# Trig_to_Gate_Converter_main_V1.net
KiCad netlist of a schematic drawn in EAGLE
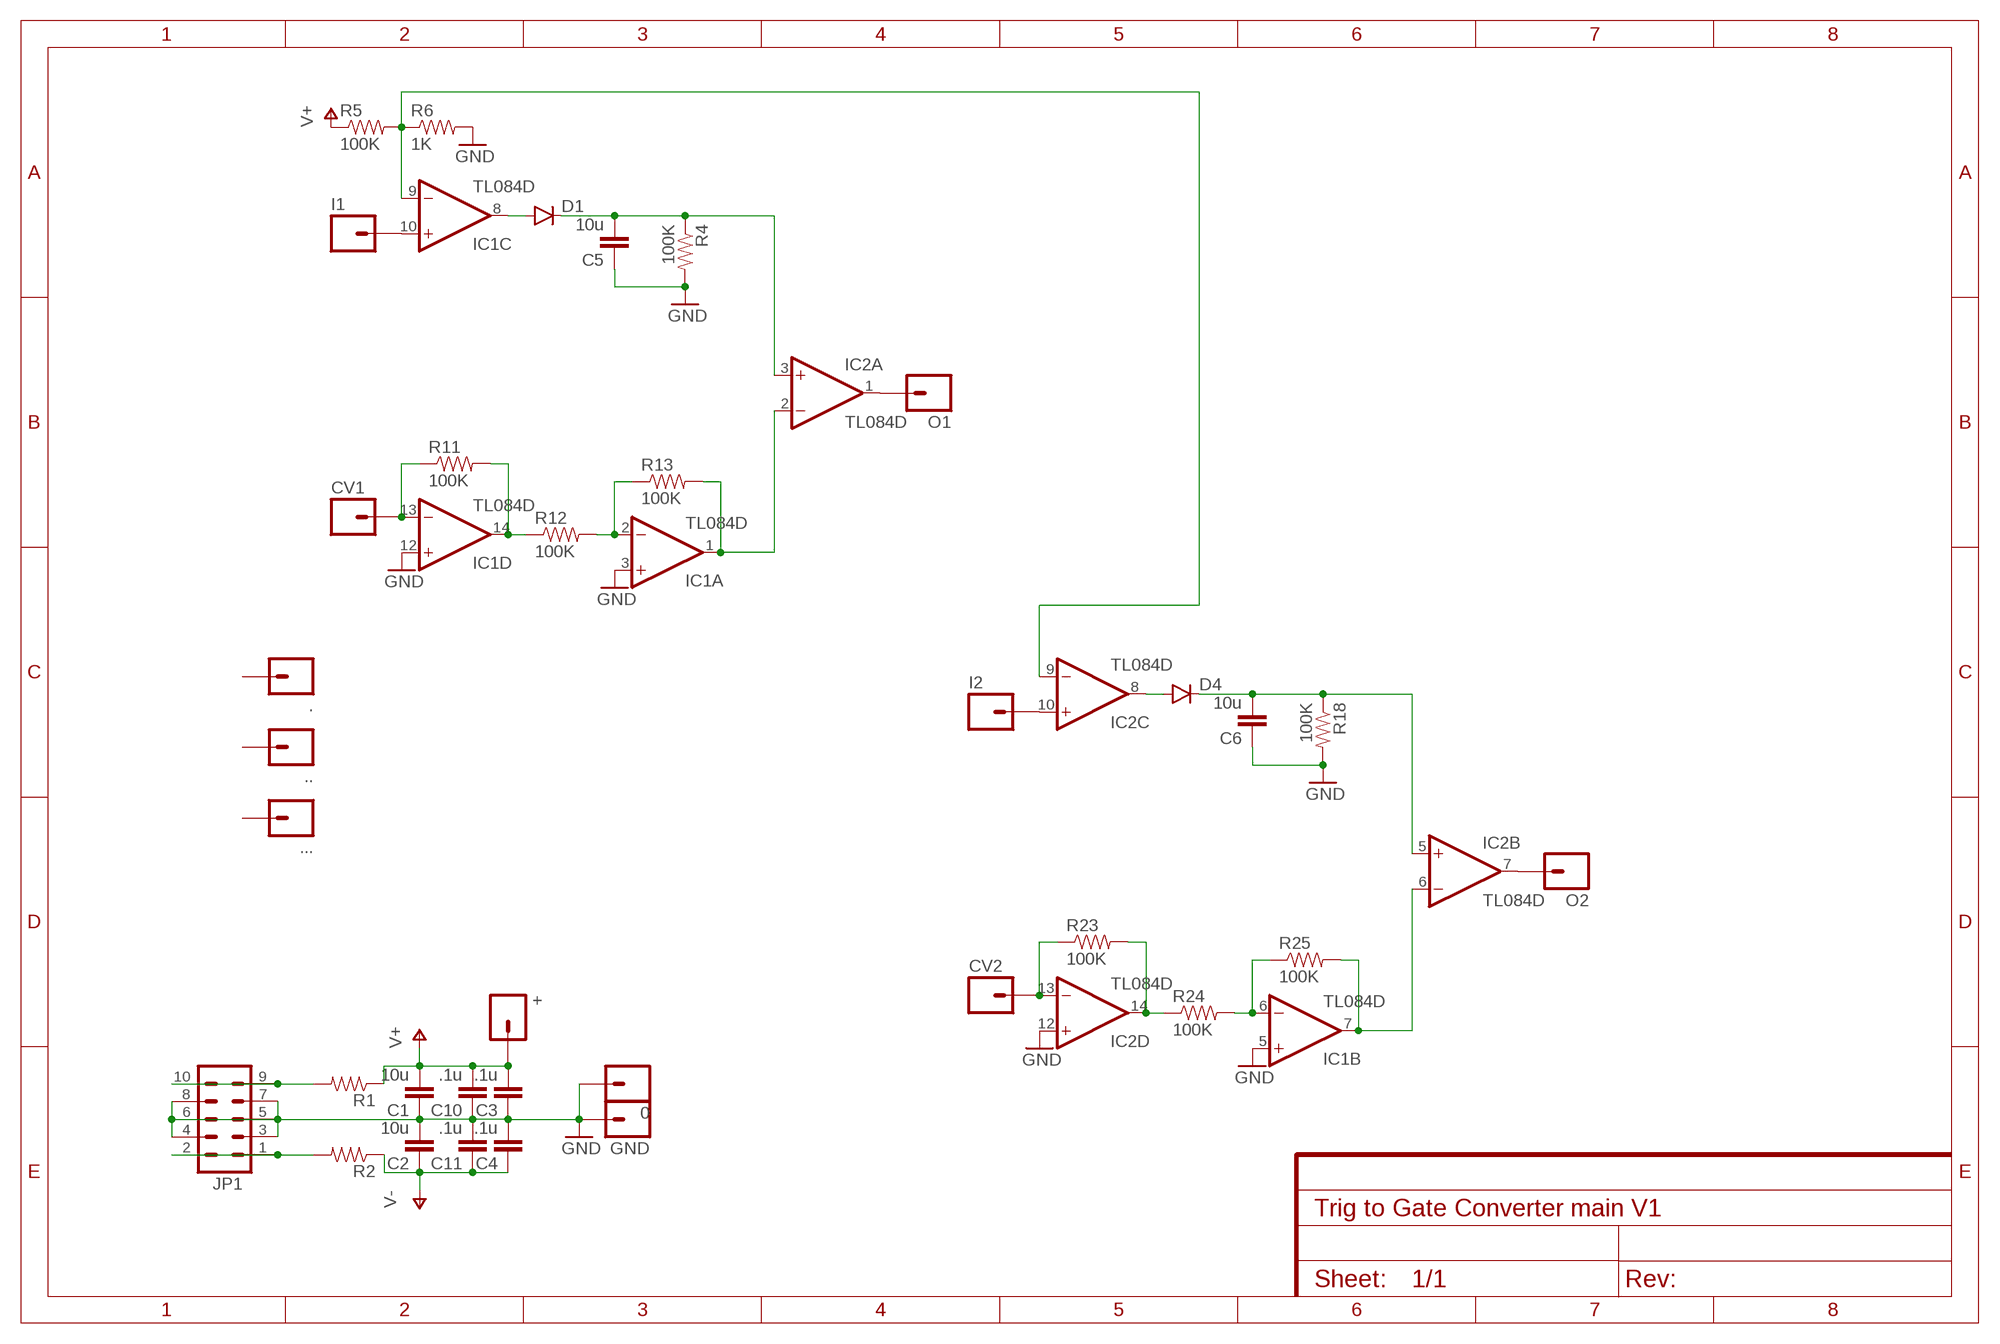
[diagram p0: schematic, sheet 1]

(export (version "E")
  (design (tool "Eeschema 10.0.6"))
  (components
    (comp (ref "+")
      (value "M01PTH")
      (footprint "eagle-import:1X01")
      (libsource (lib "eagle-import") (part "M01PTH"))
    )
    (comp (ref ".")
      (value "M01PTH")
      (footprint "eagle-import:1X01")
      (libsource (lib "eagle-import") (part "M01PTH"))
    )
    (comp (ref "..")
      (value "M01PTH")
      (footprint "eagle-import:1X01")
      (libsource (lib "eagle-import") (part "M01PTH"))
    )
    (comp (ref "...")
      (value "M01PTH")
      (footprint "eagle-import:1X01")
      (libsource (lib "eagle-import") (part "M01PTH"))
    )
    (comp (ref "0")
      (value "M01PTH")
      (footprint "eagle-import:1X01")
      (libsource (lib "eagle-import") (part "M01PTH"))
    )
    (comp (ref "C1")
      (value "10u")
      (footprint "eagle-import:1206")
      (libsource (lib "eagle-import") (part "CAP1206"))
    )
    (comp (ref "C2")
      (value "10u")
      (footprint "eagle-import:1206")
      (libsource (lib "eagle-import") (part "CAP1206"))
    )
    (comp (ref "C3")
      (value ".1u")
      (footprint "eagle-import:0805")
      (libsource (lib "eagle-import") (part "CAP0805"))
    )
    (comp (ref "C4")
      (value ".1u")
      (footprint "eagle-import:0805")
      (libsource (lib "eagle-import") (part "CAP0805"))
    )
    (comp (ref "C5")
      (value "10u")
      (footprint "eagle-import:1206")
      (libsource (lib "eagle-import") (part "CAP1206"))
    )
    (comp (ref "C6")
      (value "10u")
      (footprint "eagle-import:1206")
      (libsource (lib "eagle-import") (part "CAP1206"))
    )
    (comp (ref "C10")
      (value ".1u")
      (footprint "eagle-import:0805")
      (libsource (lib "eagle-import") (part "CAP0805"))
    )
    (comp (ref "C11")
      (value ".1u")
      (footprint "eagle-import:0805")
      (libsource (lib "eagle-import") (part "CAP0805"))
    )
    (comp (ref "CV1")
      (value "M01PTH")
      (footprint "eagle-import:1X01")
      (libsource (lib "eagle-import") (part "M01PTH"))
    )
    (comp (ref "CV2")
      (value "M01PTH")
      (footprint "eagle-import:1X01")
      (libsource (lib "eagle-import") (part "M01PTH"))
    )
    (comp (ref "D1")
      (value "DIODESOD123")
      (footprint "eagle-import:SOD-123")
      (libsource (lib "eagle-import") (part "DIODESOD123"))
    )
    (comp (ref "D4")
      (value "DIODESOD123")
      (footprint "eagle-import:SOD-123")
      (libsource (lib "eagle-import") (part "DIODESOD123"))
    )
    (comp (ref "GND")
      (value "M01PTH")
      (footprint "eagle-import:1X01")
      (libsource (lib "eagle-import") (part "M01PTH"))
    )
    (comp (ref "I1")
      (value "M01PTH")
      (footprint "eagle-import:1X01")
      (libsource (lib "eagle-import") (part "M01PTH"))
    )
    (comp (ref "I2")
      (value "M01PTH")
      (footprint "eagle-import:1X01")
      (libsource (lib "eagle-import") (part "M01PTH"))
    )
    (comp (ref "IC1")
      (value "TL084D")
      (footprint "eagle-import:SO14")
      (libsource (lib "eagle-import") (part "TL084D"))
    )
    (comp (ref "IC2")
      (value "TL084D")
      (footprint "eagle-import:SO14")
      (libsource (lib "eagle-import") (part "TL084D"))
    )
    (comp (ref "JP1")
      (value "M05X2PTH")
      (footprint "eagle-import:AVR_ICSP")
      (libsource (lib "eagle-import") (part "M05X2PTH"))
    )
    (comp (ref "O1")
      (value "M01PTH")
      (footprint "eagle-import:1X01")
      (libsource (lib "eagle-import") (part "M01PTH"))
    )
    (comp (ref "O2")
      (value "M01PTH")
      (footprint "eagle-import:1X01")
      (libsource (lib "eagle-import") (part "M01PTH"))
    )
    (comp (ref "R1")
      (value "RESISTOR0805-RES")
      (footprint "eagle-import:0805")
      (libsource (lib "eagle-import") (part "RESISTOR0805-RES"))
    )
    (comp (ref "R2")
      (value "RESISTOR0805-RES")
      (footprint "eagle-import:0805")
      (libsource (lib "eagle-import") (part "RESISTOR0805-RES"))
    )
    (comp (ref "R4")
      (value "100K")
      (footprint "eagle-import:0805")
      (libsource (lib "eagle-import") (part "RESISTOR0805-RES"))
    )
    (comp (ref "R5")
      (value "100K")
      (footprint "eagle-import:0805")
      (libsource (lib "eagle-import") (part "RESISTOR0805-RES"))
    )
    (comp (ref "R6")
      (value "1K")
      (footprint "eagle-import:0805")
      (libsource (lib "eagle-import") (part "RESISTOR0805-RES"))
    )
    (comp (ref "R11")
      (value "100K")
      (footprint "eagle-import:0805")
      (libsource (lib "eagle-import") (part "RESISTOR0805-RES"))
    )
    (comp (ref "R12")
      (value "100K")
      (footprint "eagle-import:0805")
      (libsource (lib "eagle-import") (part "RESISTOR0805-RES"))
    )
    (comp (ref "R13")
      (value "100K")
      (footprint "eagle-import:0805")
      (libsource (lib "eagle-import") (part "RESISTOR0805-RES"))
    )
    (comp (ref "R18")
      (value "100K")
      (footprint "eagle-import:0805")
      (libsource (lib "eagle-import") (part "RESISTOR0805-RES"))
    )
    (comp (ref "R23")
      (value "100K")
      (footprint "eagle-import:0805")
      (libsource (lib "eagle-import") (part "RESISTOR0805-RES"))
    )
    (comp (ref "R24")
      (value "100K")
      (footprint "eagle-import:0805")
      (libsource (lib "eagle-import") (part "RESISTOR0805-RES"))
    )
    (comp (ref "R25")
      (value "100K")
      (footprint "eagle-import:0805")
      (libsource (lib "eagle-import") (part "RESISTOR0805-RES"))
    )
  )
  (nets
    (net (code "1") (name "GND") (class "Default")
      (node (ref "0") (pin "1") (pinfunction "1_1") (pintype "passive"))
      (node (ref "C1") (pin "1") (pinfunction "1_1") (pintype "passive"))
      (node (ref "C10") (pin "1") (pinfunction "1_1") (pintype "passive"))
      (node (ref "C11") (pin "2") (pinfunction "2_2") (pintype "passive"))
      (node (ref "C2") (pin "2") (pinfunction "2_2") (pintype "passive"))
      (node (ref "C3") (pin "1") (pinfunction "1_1") (pintype "passive"))
      (node (ref "C4") (pin "2") (pinfunction "2_2") (pintype "passive"))
      (node (ref "C5") (pin "1") (pinfunction "1_1") (pintype "passive"))
      (node (ref "C6") (pin "1") (pinfunction "1_1") (pintype "passive"))
      (node (ref "GND") (pin "1") (pinfunction "1_1") (pintype "passive"))
      (node (ref "IC1") (pin "12") (pinfunction "+IN_12") (pintype "input"))
      (node (ref "IC1") (pin "3") (pinfunction "+IN_3") (pintype "input"))
      (node (ref "IC1") (pin "5") (pinfunction "+IN_5") (pintype "input"))
      (node (ref "IC2") (pin "12") (pinfunction "+IN_12") (pintype "input"))
      (node (ref "JP1") (pin "3") (pinfunction "3_3") (pintype "passive"))
      (node (ref "JP1") (pin "4") (pinfunction "4_4") (pintype "passive"))
      (node (ref "JP1") (pin "5") (pinfunction "5_5") (pintype "passive"))
      (node (ref "JP1") (pin "6") (pinfunction "6_6") (pintype "passive"))
      (node (ref "JP1") (pin "7") (pinfunction "7_7") (pintype "passive"))
      (node (ref "JP1") (pin "8") (pinfunction "8_8") (pintype "passive"))
      (node (ref "R18") (pin "2") (pinfunction "2_2") (pintype "passive"))
      (node (ref "R4") (pin "2") (pinfunction "2_2") (pintype "passive"))
      (node (ref "R6") (pin "2") (pinfunction "2_2") (pintype "passive"))
    )
    (net (code "2") (name "Net-(IC1A--IN)") (class "Default")
      (node (ref "IC1") (pin "2") (pinfunction "-IN_2") (pintype "input"))
      (node (ref "R12") (pin "2") (pinfunction "2_2") (pintype "passive"))
      (node (ref "R13") (pin "1") (pinfunction "1_1") (pintype "passive"))
    )
    (net (code "3") (name "Net-(IC1A-OUT)") (class "Default")
      (node (ref "IC1") (pin "1") (pinfunction "OUT_1") (pintype "output"))
      (node (ref "IC2") (pin "2") (pinfunction "-IN_2") (pintype "input"))
      (node (ref "R13") (pin "2") (pinfunction "2_2") (pintype "passive"))
    )
    (net (code "4") (name "Net-(IC1B--IN)") (class "Default")
      (node (ref "IC1") (pin "6") (pinfunction "-IN_6") (pintype "input"))
      (node (ref "R24") (pin "2") (pinfunction "2_2") (pintype "passive"))
      (node (ref "R25") (pin "1") (pinfunction "1_1") (pintype "passive"))
    )
    (net (code "5") (name "Net-(IC1B-OUT)") (class "Default")
      (node (ref "IC1") (pin "7") (pinfunction "OUT_7") (pintype "output"))
      (node (ref "IC2") (pin "6") (pinfunction "-IN_6") (pintype "input"))
      (node (ref "R25") (pin "2") (pinfunction "2_2") (pintype "passive"))
    )
    (net (code "6") (name "Net-(IC1C-+IN)") (class "Default")
      (node (ref "I1") (pin "1") (pinfunction "1_1") (pintype "passive"))
      (node (ref "IC1") (pin "10") (pinfunction "+IN_10") (pintype "input"))
    )
    (net (code "7") (name "Net-(IC1C--IN)") (class "Default")
      (node (ref "IC1") (pin "9") (pinfunction "-IN_9") (pintype "input"))
      (node (ref "IC2") (pin "9") (pinfunction "-IN_9") (pintype "input"))
      (node (ref "R5") (pin "2") (pinfunction "2_2") (pintype "passive"))
      (node (ref "R6") (pin "1") (pinfunction "1_1") (pintype "passive"))
    )
    (net (code "8") (name "Net-(IC1C-OUT)") (class "Default")
      (node (ref "D1") (pin "A") (pinfunction "A_A") (pintype "passive"))
      (node (ref "IC1") (pin "8") (pinfunction "OUT_8") (pintype "output"))
    )
    (net (code "9") (name "Net-(IC1D--IN)") (class "Default")
      (node (ref "CV1") (pin "1") (pinfunction "1_1") (pintype "passive"))
      (node (ref "IC1") (pin "13") (pinfunction "-IN_13") (pintype "input"))
      (node (ref "R11") (pin "1") (pinfunction "1_1") (pintype "passive"))
    )
    (net (code "10") (name "Net-(IC1D-OUT)") (class "Default")
      (node (ref "IC1") (pin "14") (pinfunction "OUT_14") (pintype "output"))
      (node (ref "R11") (pin "2") (pinfunction "2_2") (pintype "passive"))
      (node (ref "R12") (pin "1") (pinfunction "1_1") (pintype "passive"))
    )
    (net (code "11") (name "Net-(IC2A-+IN)") (class "Default")
      (node (ref "C5") (pin "2") (pinfunction "2_2") (pintype "passive"))
      (node (ref "D1") (pin "C") (pinfunction "C_C") (pintype "passive"))
      (node (ref "IC2") (pin "3") (pinfunction "+IN_3") (pintype "input"))
      (node (ref "R4") (pin "1") (pinfunction "1_1") (pintype "passive"))
    )
    (net (code "12") (name "Net-(IC2A-OUT)") (class "Default")
      (node (ref "IC2") (pin "1") (pinfunction "OUT_1") (pintype "output"))
      (node (ref "O1") (pin "1") (pinfunction "1_1") (pintype "passive"))
    )
    (net (code "13") (name "Net-(IC2B-+IN)") (class "Default")
      (node (ref "C6") (pin "2") (pinfunction "2_2") (pintype "passive"))
      (node (ref "D4") (pin "C") (pinfunction "C_C") (pintype "passive"))
      (node (ref "IC2") (pin "5") (pinfunction "+IN_5") (pintype "input"))
      (node (ref "R18") (pin "1") (pinfunction "1_1") (pintype "passive"))
    )
    (net (code "14") (name "Net-(IC2B-OUT)") (class "Default")
      (node (ref "IC2") (pin "7") (pinfunction "OUT_7") (pintype "output"))
      (node (ref "O2") (pin "1") (pinfunction "1_1") (pintype "passive"))
    )
    (net (code "15") (name "Net-(IC2C-+IN)") (class "Default")
      (node (ref "I2") (pin "1") (pinfunction "1_1") (pintype "passive"))
      (node (ref "IC2") (pin "10") (pinfunction "+IN_10") (pintype "input"))
    )
    (net (code "16") (name "Net-(IC2C-OUT)") (class "Default")
      (node (ref "D4") (pin "A") (pinfunction "A_A") (pintype "passive"))
      (node (ref "IC2") (pin "8") (pinfunction "OUT_8") (pintype "output"))
    )
    (net (code "17") (name "Net-(IC2D--IN)") (class "Default")
      (node (ref "CV2") (pin "1") (pinfunction "1_1") (pintype "passive"))
      (node (ref "IC2") (pin "13") (pinfunction "-IN_13") (pintype "input"))
      (node (ref "R23") (pin "1") (pinfunction "1_1") (pintype "passive"))
    )
    (net (code "18") (name "Net-(IC2D-OUT)") (class "Default")
      (node (ref "IC2") (pin "14") (pinfunction "OUT_14") (pintype "output"))
      (node (ref "R23") (pin "2") (pinfunction "2_2") (pintype "passive"))
      (node (ref "R24") (pin "1") (pinfunction "1_1") (pintype "passive"))
    )
    (net (code "19") (name "Net-(JP1-Pad1)") (class "Default")
      (node (ref "JP1") (pin "1") (pinfunction "1_1") (pintype "passive"))
      (node (ref "JP1") (pin "2") (pinfunction "2_2") (pintype "passive"))
      (node (ref "R2") (pin "2") (pinfunction "2_2") (pintype "passive"))
    )
    (net (code "20") (name "Net-(JP1-Pad10)") (class "Default")
      (node (ref "JP1") (pin "10") (pinfunction "10_10") (pintype "passive"))
      (node (ref "JP1") (pin "9") (pinfunction "9_9") (pintype "passive"))
      (node (ref "R1") (pin "2") (pinfunction "2_2") (pintype "passive"))
    )
    (net (code "21") (name "V+") (class "Default")
      (node (ref "+") (pin "1") (pinfunction "1_1") (pintype "passive"))
      (node (ref "C1") (pin "2") (pinfunction "2_2") (pintype "passive"))
      (node (ref "C10") (pin "2") (pinfunction "2_2") (pintype "passive"))
      (node (ref "C3") (pin "2") (pinfunction "2_2") (pintype "passive"))
      (node (ref "R1") (pin "1") (pinfunction "1_1") (pintype "passive"))
      (node (ref "R5") (pin "1") (pinfunction "1_1") (pintype "passive"))
    )
    (net (code "22") (name "V-") (class "Default")
      (node (ref "C11") (pin "1") (pinfunction "1_1") (pintype "passive"))
      (node (ref "C2") (pin "1") (pinfunction "1_1") (pintype "passive"))
      (node (ref "C4") (pin "1") (pinfunction "1_1") (pintype "passive"))
      (node (ref "R2") (pin "1") (pinfunction "1_1") (pintype "passive"))
    )
    (net (code "23") (name "unconnected-(.-Pad1)") (class "Default")
      (node (ref ".") (pin "1") (pinfunction "1_1") (pintype "passive"))
    )
    (net (code "24") (name "unconnected-(..-Pad1)") (class "Default")
      (node (ref "..") (pin "1") (pinfunction "1_1") (pintype "passive"))
    )
    (net (code "25") (name "unconnected-(...-Pad1)") (class "Default")
      (node (ref "...") (pin "1") (pinfunction "1_1") (pintype "passive"))
    )
  )
)
